# TestBoard.net
KiCad netlist of a schematic drawn in Altium Designer
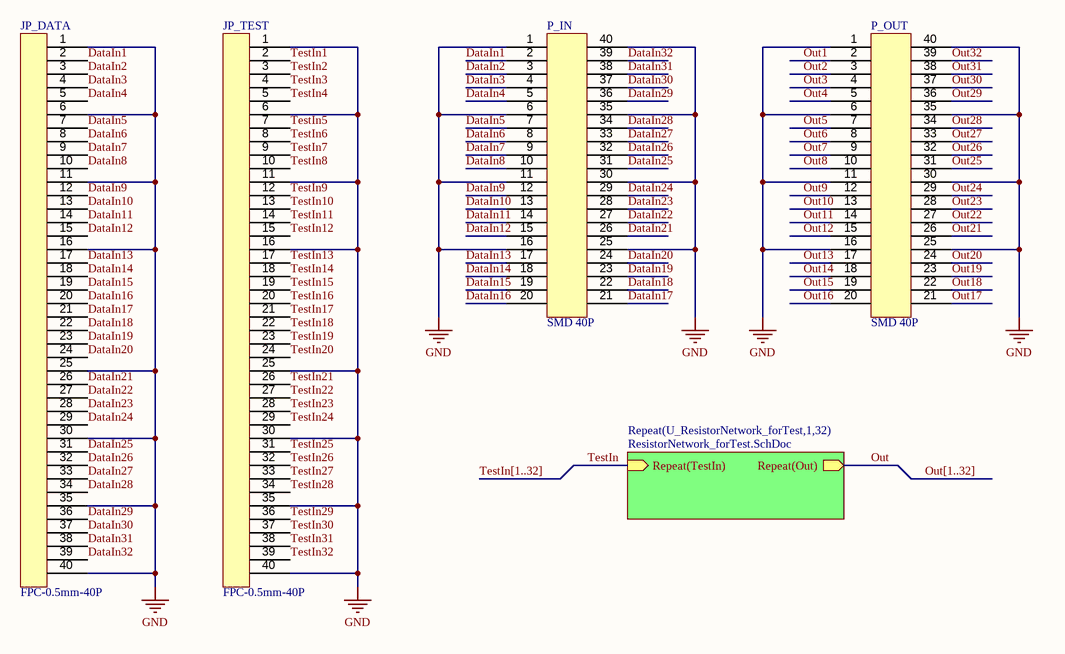
[diagram p0: TestBoard.SchDoc]

(export (version "E")
  (design (tool "Eeschema 10.0.6"))
  (components
    (comp (ref "JP_DATA")
      (value "FPC-0.5mm-40P")
      (footprint "FPC0.5 2H-WS-40P")
      (description "FPC Connector 0.5mm 40PIN")
      (libsource (lib "CustomizedComponents") (part "FPC-0.5mm-40P"))
    )
    (comp (ref "JP_TEST")
      (value "FPC-0.5mm-40P")
      (footprint "FPC0.5 2H-WS-40P")
      (description "FPC Connector 0.5mm 40PIN")
      (libsource (lib "CustomizedComponents") (part "FPC-0.5mm-40P"))
    )
    (comp (ref "P_IN")
      (value "SMD 40P")
      (footprint "SMD-40P-W0.2-H0.6-T0.4")
      (description "SMD Pad for Chip Bonding (40 PIN).")
      (libsource (lib "CustomizedComponents") (part "SMD 40P"))
    )
    (comp (ref "P_OUT")
      (value "SMD 40P")
      (footprint "SMD-40P-W0.2-H0.6-T0.4")
      (description "SMD Pad for Chip Bonding (40 PIN).")
      (libsource (lib "CustomizedComponents") (part "SMD 40P"))
    )
  )
  (nets
    (net (code "1") (name "/DataIn1") (class "Default")
      (node (ref "JP_DATA") (pin "2") (pintype "passive"))
      (node (ref "P_IN") (pin "2") (pintype "passive"))
    )
    (net (code "2") (name "/DataIn2") (class "Default")
      (node (ref "JP_DATA") (pin "3") (pintype "passive"))
      (node (ref "P_IN") (pin "3") (pintype "passive"))
    )
    (net (code "3") (name "/DataIn3") (class "Default")
      (node (ref "JP_DATA") (pin "4") (pintype "passive"))
      (node (ref "P_IN") (pin "4") (pintype "passive"))
    )
    (net (code "4") (name "/DataIn4") (class "Default")
      (node (ref "JP_DATA") (pin "5") (pintype "passive"))
      (node (ref "P_IN") (pin "5") (pintype "passive"))
    )
    (net (code "5") (name "/DataIn5") (class "Default")
      (node (ref "JP_DATA") (pin "7") (pintype "passive"))
      (node (ref "P_IN") (pin "7") (pintype "passive"))
    )
    (net (code "6") (name "/DataIn6") (class "Default")
      (node (ref "JP_DATA") (pin "8") (pintype "passive"))
      (node (ref "P_IN") (pin "8") (pintype "passive"))
    )
    (net (code "7") (name "/DataIn7") (class "Default")
      (node (ref "JP_DATA") (pin "9") (pintype "passive"))
      (node (ref "P_IN") (pin "9") (pintype "passive"))
    )
    (net (code "8") (name "/DataIn8") (class "Default")
      (node (ref "JP_DATA") (pin "10") (pintype "passive"))
      (node (ref "P_IN") (pin "10") (pintype "passive"))
    )
    (net (code "9") (name "/DataIn9") (class "Default")
      (node (ref "JP_DATA") (pin "12") (pintype "passive"))
      (node (ref "P_IN") (pin "12") (pintype "passive"))
    )
    (net (code "10") (name "/DataIn10") (class "Default")
      (node (ref "JP_DATA") (pin "13") (pintype "passive"))
      (node (ref "P_IN") (pin "13") (pintype "passive"))
    )
    (net (code "11") (name "/DataIn11") (class "Default")
      (node (ref "JP_DATA") (pin "14") (pintype "passive"))
      (node (ref "P_IN") (pin "14") (pintype "passive"))
    )
    (net (code "12") (name "/DataIn12") (class "Default")
      (node (ref "JP_DATA") (pin "15") (pintype "passive"))
      (node (ref "P_IN") (pin "15") (pintype "passive"))
    )
    (net (code "13") (name "/DataIn13") (class "Default")
      (node (ref "JP_DATA") (pin "17") (pintype "passive"))
      (node (ref "P_IN") (pin "17") (pintype "passive"))
    )
    (net (code "14") (name "/DataIn14") (class "Default")
      (node (ref "JP_DATA") (pin "18") (pintype "passive"))
      (node (ref "P_IN") (pin "18") (pintype "passive"))
    )
    (net (code "15") (name "/DataIn15") (class "Default")
      (node (ref "JP_DATA") (pin "19") (pintype "passive"))
      (node (ref "P_IN") (pin "19") (pintype "passive"))
    )
    (net (code "16") (name "/DataIn16") (class "Default")
      (node (ref "JP_DATA") (pin "20") (pintype "passive"))
      (node (ref "P_IN") (pin "20") (pintype "passive"))
    )
    (net (code "17") (name "/DataIn17") (class "Default")
      (node (ref "JP_DATA") (pin "21") (pintype "passive"))
      (node (ref "P_IN") (pin "21") (pintype "passive"))
    )
    (net (code "18") (name "/DataIn18") (class "Default")
      (node (ref "JP_DATA") (pin "22") (pintype "passive"))
      (node (ref "P_IN") (pin "22") (pintype "passive"))
    )
    (net (code "19") (name "/DataIn19") (class "Default")
      (node (ref "JP_DATA") (pin "23") (pintype "passive"))
      (node (ref "P_IN") (pin "23") (pintype "passive"))
    )
    (net (code "20") (name "/DataIn20") (class "Default")
      (node (ref "JP_DATA") (pin "24") (pintype "passive"))
      (node (ref "P_IN") (pin "24") (pintype "passive"))
    )
    (net (code "21") (name "/DataIn21") (class "Default")
      (node (ref "JP_DATA") (pin "26") (pintype "passive"))
      (node (ref "P_IN") (pin "26") (pintype "passive"))
    )
    (net (code "22") (name "/DataIn22") (class "Default")
      (node (ref "JP_DATA") (pin "27") (pintype "passive"))
      (node (ref "P_IN") (pin "27") (pintype "passive"))
    )
    (net (code "23") (name "/DataIn23") (class "Default")
      (node (ref "JP_DATA") (pin "28") (pintype "passive"))
      (node (ref "P_IN") (pin "28") (pintype "passive"))
    )
    (net (code "24") (name "/DataIn24") (class "Default")
      (node (ref "JP_DATA") (pin "29") (pintype "passive"))
      (node (ref "P_IN") (pin "29") (pintype "passive"))
    )
    (net (code "25") (name "/DataIn25") (class "Default")
      (node (ref "JP_DATA") (pin "31") (pintype "passive"))
      (node (ref "P_IN") (pin "31") (pintype "passive"))
    )
    (net (code "26") (name "/DataIn26") (class "Default")
      (node (ref "JP_DATA") (pin "32") (pintype "passive"))
      (node (ref "P_IN") (pin "32") (pintype "passive"))
    )
    (net (code "27") (name "/DataIn27") (class "Default")
      (node (ref "JP_DATA") (pin "33") (pintype "passive"))
      (node (ref "P_IN") (pin "33") (pintype "passive"))
    )
    (net (code "28") (name "/DataIn28") (class "Default")
      (node (ref "JP_DATA") (pin "34") (pintype "passive"))
      (node (ref "P_IN") (pin "34") (pintype "passive"))
    )
    (net (code "29") (name "/DataIn29") (class "Default")
      (node (ref "JP_DATA") (pin "36") (pintype "passive"))
      (node (ref "P_IN") (pin "36") (pintype "passive"))
    )
    (net (code "30") (name "/DataIn30") (class "Default")
      (node (ref "JP_DATA") (pin "37") (pintype "passive"))
      (node (ref "P_IN") (pin "37") (pintype "passive"))
    )
    (net (code "31") (name "/DataIn31") (class "Default")
      (node (ref "JP_DATA") (pin "38") (pintype "passive"))
      (node (ref "P_IN") (pin "38") (pintype "passive"))
    )
    (net (code "32") (name "/DataIn32") (class "Default")
      (node (ref "JP_DATA") (pin "39") (pintype "passive"))
      (node (ref "P_IN") (pin "39") (pintype "passive"))
    )
    (net (code "34") (name "/Out1") (class "Default") (node (ref "P_OUT") (pin "2") (pintype "passive")))
    (net (code "35") (name "/Out2") (class "Default") (node (ref "P_OUT") (pin "3") (pintype "passive")))
    (net (code "36") (name "/Out3") (class "Default") (node (ref "P_OUT") (pin "4") (pintype "passive")))
    (net (code "37") (name "/Out4") (class "Default") (node (ref "P_OUT") (pin "5") (pintype "passive")))
    (net (code "38") (name "/Out5") (class "Default") (node (ref "P_OUT") (pin "7") (pintype "passive")))
    (net (code "39") (name "/Out6") (class "Default") (node (ref "P_OUT") (pin "8") (pintype "passive")))
    (net (code "40") (name "/Out7") (class "Default") (node (ref "P_OUT") (pin "9") (pintype "passive")))
    (net (code "41") (name "/Out8") (class "Default") (node (ref "P_OUT") (pin "10") (pintype "passive")))
    (net (code "42") (name "/Out9") (class "Default") (node (ref "P_OUT") (pin "12") (pintype "passive")))
    (net (code "43") (name "/Out10") (class "Default") (node (ref "P_OUT") (pin "13") (pintype "passive")))
    (net (code "44") (name "/Out11") (class "Default") (node (ref "P_OUT") (pin "14") (pintype "passive")))
    (net (code "45") (name "/Out12") (class "Default") (node (ref "P_OUT") (pin "15") (pintype "passive")))
    (net (code "46") (name "/Out13") (class "Default") (node (ref "P_OUT") (pin "17") (pintype "passive")))
    (net (code "47") (name "/Out14") (class "Default") (node (ref "P_OUT") (pin "18") (pintype "passive")))
    (net (code "48") (name "/Out15") (class "Default") (node (ref "P_OUT") (pin "19") (pintype "passive")))
    (net (code "49") (name "/Out16") (class "Default") (node (ref "P_OUT") (pin "20") (pintype "passive")))
    (net (code "50") (name "/Out17") (class "Default") (node (ref "P_OUT") (pin "21") (pintype "passive")))
    (net (code "51") (name "/Out18") (class "Default") (node (ref "P_OUT") (pin "22") (pintype "passive")))
    (net (code "52") (name "/Out19") (class "Default") (node (ref "P_OUT") (pin "23") (pintype "passive")))
    (net (code "53") (name "/Out20") (class "Default") (node (ref "P_OUT") (pin "24") (pintype "passive")))
    (net (code "54") (name "/Out21") (class "Default") (node (ref "P_OUT") (pin "26") (pintype "passive")))
    (net (code "55") (name "/Out22") (class "Default") (node (ref "P_OUT") (pin "27") (pintype "passive")))
    (net (code "56") (name "/Out23") (class "Default") (node (ref "P_OUT") (pin "28") (pintype "passive")))
    (net (code "57") (name "/Out24") (class "Default") (node (ref "P_OUT") (pin "29") (pintype "passive")))
    (net (code "58") (name "/Out25") (class "Default") (node (ref "P_OUT") (pin "31") (pintype "passive")))
    (net (code "59") (name "/Out26") (class "Default") (node (ref "P_OUT") (pin "32") (pintype "passive")))
    (net (code "60") (name "/Out27") (class "Default") (node (ref "P_OUT") (pin "33") (pintype "passive")))
    (net (code "61") (name "/Out28") (class "Default") (node (ref "P_OUT") (pin "34") (pintype "passive")))
    (net (code "62") (name "/Out29") (class "Default") (node (ref "P_OUT") (pin "36") (pintype "passive")))
    (net (code "63") (name "/Out30") (class "Default") (node (ref "P_OUT") (pin "37") (pintype "passive")))
    (net (code "64") (name "/Out31") (class "Default") (node (ref "P_OUT") (pin "38") (pintype "passive")))
    (net (code "65") (name "/Out32") (class "Default") (node (ref "P_OUT") (pin "39") (pintype "passive")))
    (net (code "68") (name "/TestIn1") (class "Default") (node (ref "JP_TEST") (pin "2") (pintype "passive")))
    (net (code "69") (name "/TestIn2") (class "Default") (node (ref "JP_TEST") (pin "3") (pintype "passive")))
    (net (code "70") (name "/TestIn3") (class "Default") (node (ref "JP_TEST") (pin "4") (pintype "passive")))
    (net (code "71") (name "/TestIn4") (class "Default") (node (ref "JP_TEST") (pin "5") (pintype "passive")))
    (net (code "72") (name "/TestIn5") (class "Default") (node (ref "JP_TEST") (pin "7") (pintype "passive")))
    (net (code "73") (name "/TestIn6") (class "Default") (node (ref "JP_TEST") (pin "8") (pintype "passive")))
    (net (code "74") (name "/TestIn7") (class "Default") (node (ref "JP_TEST") (pin "9") (pintype "passive")))
    (net (code "75") (name "/TestIn8") (class "Default")
      (node (ref "JP_TEST") (pin "10") (pintype "passive"))
    )
    (net (code "76") (name "/TestIn9") (class "Default")
      (node (ref "JP_TEST") (pin "12") (pintype "passive"))
    )
    (net (code "77") (name "/TestIn10") (class "Default")
      (node (ref "JP_TEST") (pin "13") (pintype "passive"))
    )
    (net (code "78") (name "/TestIn11") (class "Default")
      (node (ref "JP_TEST") (pin "14") (pintype "passive"))
    )
    (net (code "79") (name "/TestIn12") (class "Default")
      (node (ref "JP_TEST") (pin "15") (pintype "passive"))
    )
    (net (code "80") (name "/TestIn13") (class "Default")
      (node (ref "JP_TEST") (pin "17") (pintype "passive"))
    )
    (net (code "81") (name "/TestIn14") (class "Default")
      (node (ref "JP_TEST") (pin "18") (pintype "passive"))
    )
    (net (code "82") (name "/TestIn15") (class "Default")
      (node (ref "JP_TEST") (pin "19") (pintype "passive"))
    )
    (net (code "83") (name "/TestIn16") (class "Default")
      (node (ref "JP_TEST") (pin "20") (pintype "passive"))
    )
    (net (code "84") (name "/TestIn17") (class "Default")
      (node (ref "JP_TEST") (pin "21") (pintype "passive"))
    )
    (net (code "85") (name "/TestIn18") (class "Default")
      (node (ref "JP_TEST") (pin "22") (pintype "passive"))
    )
    (net (code "86") (name "/TestIn19") (class "Default")
      (node (ref "JP_TEST") (pin "23") (pintype "passive"))
    )
    (net (code "87") (name "/TestIn20") (class "Default")
      (node (ref "JP_TEST") (pin "24") (pintype "passive"))
    )
    (net (code "88") (name "/TestIn21") (class "Default")
      (node (ref "JP_TEST") (pin "26") (pintype "passive"))
    )
    (net (code "89") (name "/TestIn22") (class "Default")
      (node (ref "JP_TEST") (pin "27") (pintype "passive"))
    )
    (net (code "90") (name "/TestIn23") (class "Default")
      (node (ref "JP_TEST") (pin "28") (pintype "passive"))
    )
    (net (code "91") (name "/TestIn24") (class "Default")
      (node (ref "JP_TEST") (pin "29") (pintype "passive"))
    )
    (net (code "92") (name "/TestIn25") (class "Default")
      (node (ref "JP_TEST") (pin "31") (pintype "passive"))
    )
    (net (code "93") (name "/TestIn26") (class "Default")
      (node (ref "JP_TEST") (pin "32") (pintype "passive"))
    )
    (net (code "94") (name "/TestIn27") (class "Default")
      (node (ref "JP_TEST") (pin "33") (pintype "passive"))
    )
    (net (code "95") (name "/TestIn28") (class "Default")
      (node (ref "JP_TEST") (pin "34") (pintype "passive"))
    )
    (net (code "96") (name "/TestIn29") (class "Default")
      (node (ref "JP_TEST") (pin "36") (pintype "passive"))
    )
    (net (code "97") (name "/TestIn30") (class "Default")
      (node (ref "JP_TEST") (pin "37") (pintype "passive"))
    )
    (net (code "98") (name "/TestIn31") (class "Default")
      (node (ref "JP_TEST") (pin "38") (pintype "passive"))
    )
    (net (code "99") (name "/TestIn32") (class "Default")
      (node (ref "JP_TEST") (pin "39") (pintype "passive"))
    )
    (net (code "101") (name "GND") (class "Default")
      (node (ref "JP_DATA") (pin "1") (pintype "passive"))
      (node (ref "JP_DATA") (pin "11") (pintype "passive"))
      (node (ref "JP_DATA") (pin "16") (pintype "passive"))
      (node (ref "JP_DATA") (pin "25") (pintype "passive"))
      (node (ref "JP_DATA") (pin "30") (pintype "passive"))
      (node (ref "JP_DATA") (pin "35") (pintype "passive"))
      (node (ref "JP_DATA") (pin "40") (pintype "passive"))
      (node (ref "JP_DATA") (pin "6") (pintype "passive"))
      (node (ref "JP_TEST") (pin "1") (pintype "passive"))
      (node (ref "JP_TEST") (pin "11") (pintype "passive"))
      (node (ref "JP_TEST") (pin "16") (pintype "passive"))
      (node (ref "JP_TEST") (pin "25") (pintype "passive"))
      (node (ref "JP_TEST") (pin "30") (pintype "passive"))
      (node (ref "JP_TEST") (pin "35") (pintype "passive"))
      (node (ref "JP_TEST") (pin "40") (pintype "passive"))
      (node (ref "JP_TEST") (pin "6") (pintype "passive"))
      (node (ref "P_IN") (pin "1") (pintype "passive"))
      (node (ref "P_IN") (pin "11") (pintype "passive"))
      (node (ref "P_IN") (pin "16") (pintype "passive"))
      (node (ref "P_IN") (pin "25") (pintype "passive"))
      (node (ref "P_IN") (pin "30") (pintype "passive"))
      (node (ref "P_IN") (pin "35") (pintype "passive"))
      (node (ref "P_IN") (pin "40") (pintype "passive"))
      (node (ref "P_IN") (pin "6") (pintype "passive"))
      (node (ref "P_OUT") (pin "1") (pintype "passive"))
      (node (ref "P_OUT") (pin "11") (pintype "passive"))
      (node (ref "P_OUT") (pin "16") (pintype "passive"))
      (node (ref "P_OUT") (pin "25") (pintype "passive"))
      (node (ref "P_OUT") (pin "30") (pintype "passive"))
      (node (ref "P_OUT") (pin "35") (pintype "passive"))
      (node (ref "P_OUT") (pin "40") (pintype "passive"))
      (node (ref "P_OUT") (pin "6") (pintype "passive"))
    )
  )
)
